# connect_4_robot_trimer_for_sensor.net
KiCad netlist of a schematic drawn in EasyEDA
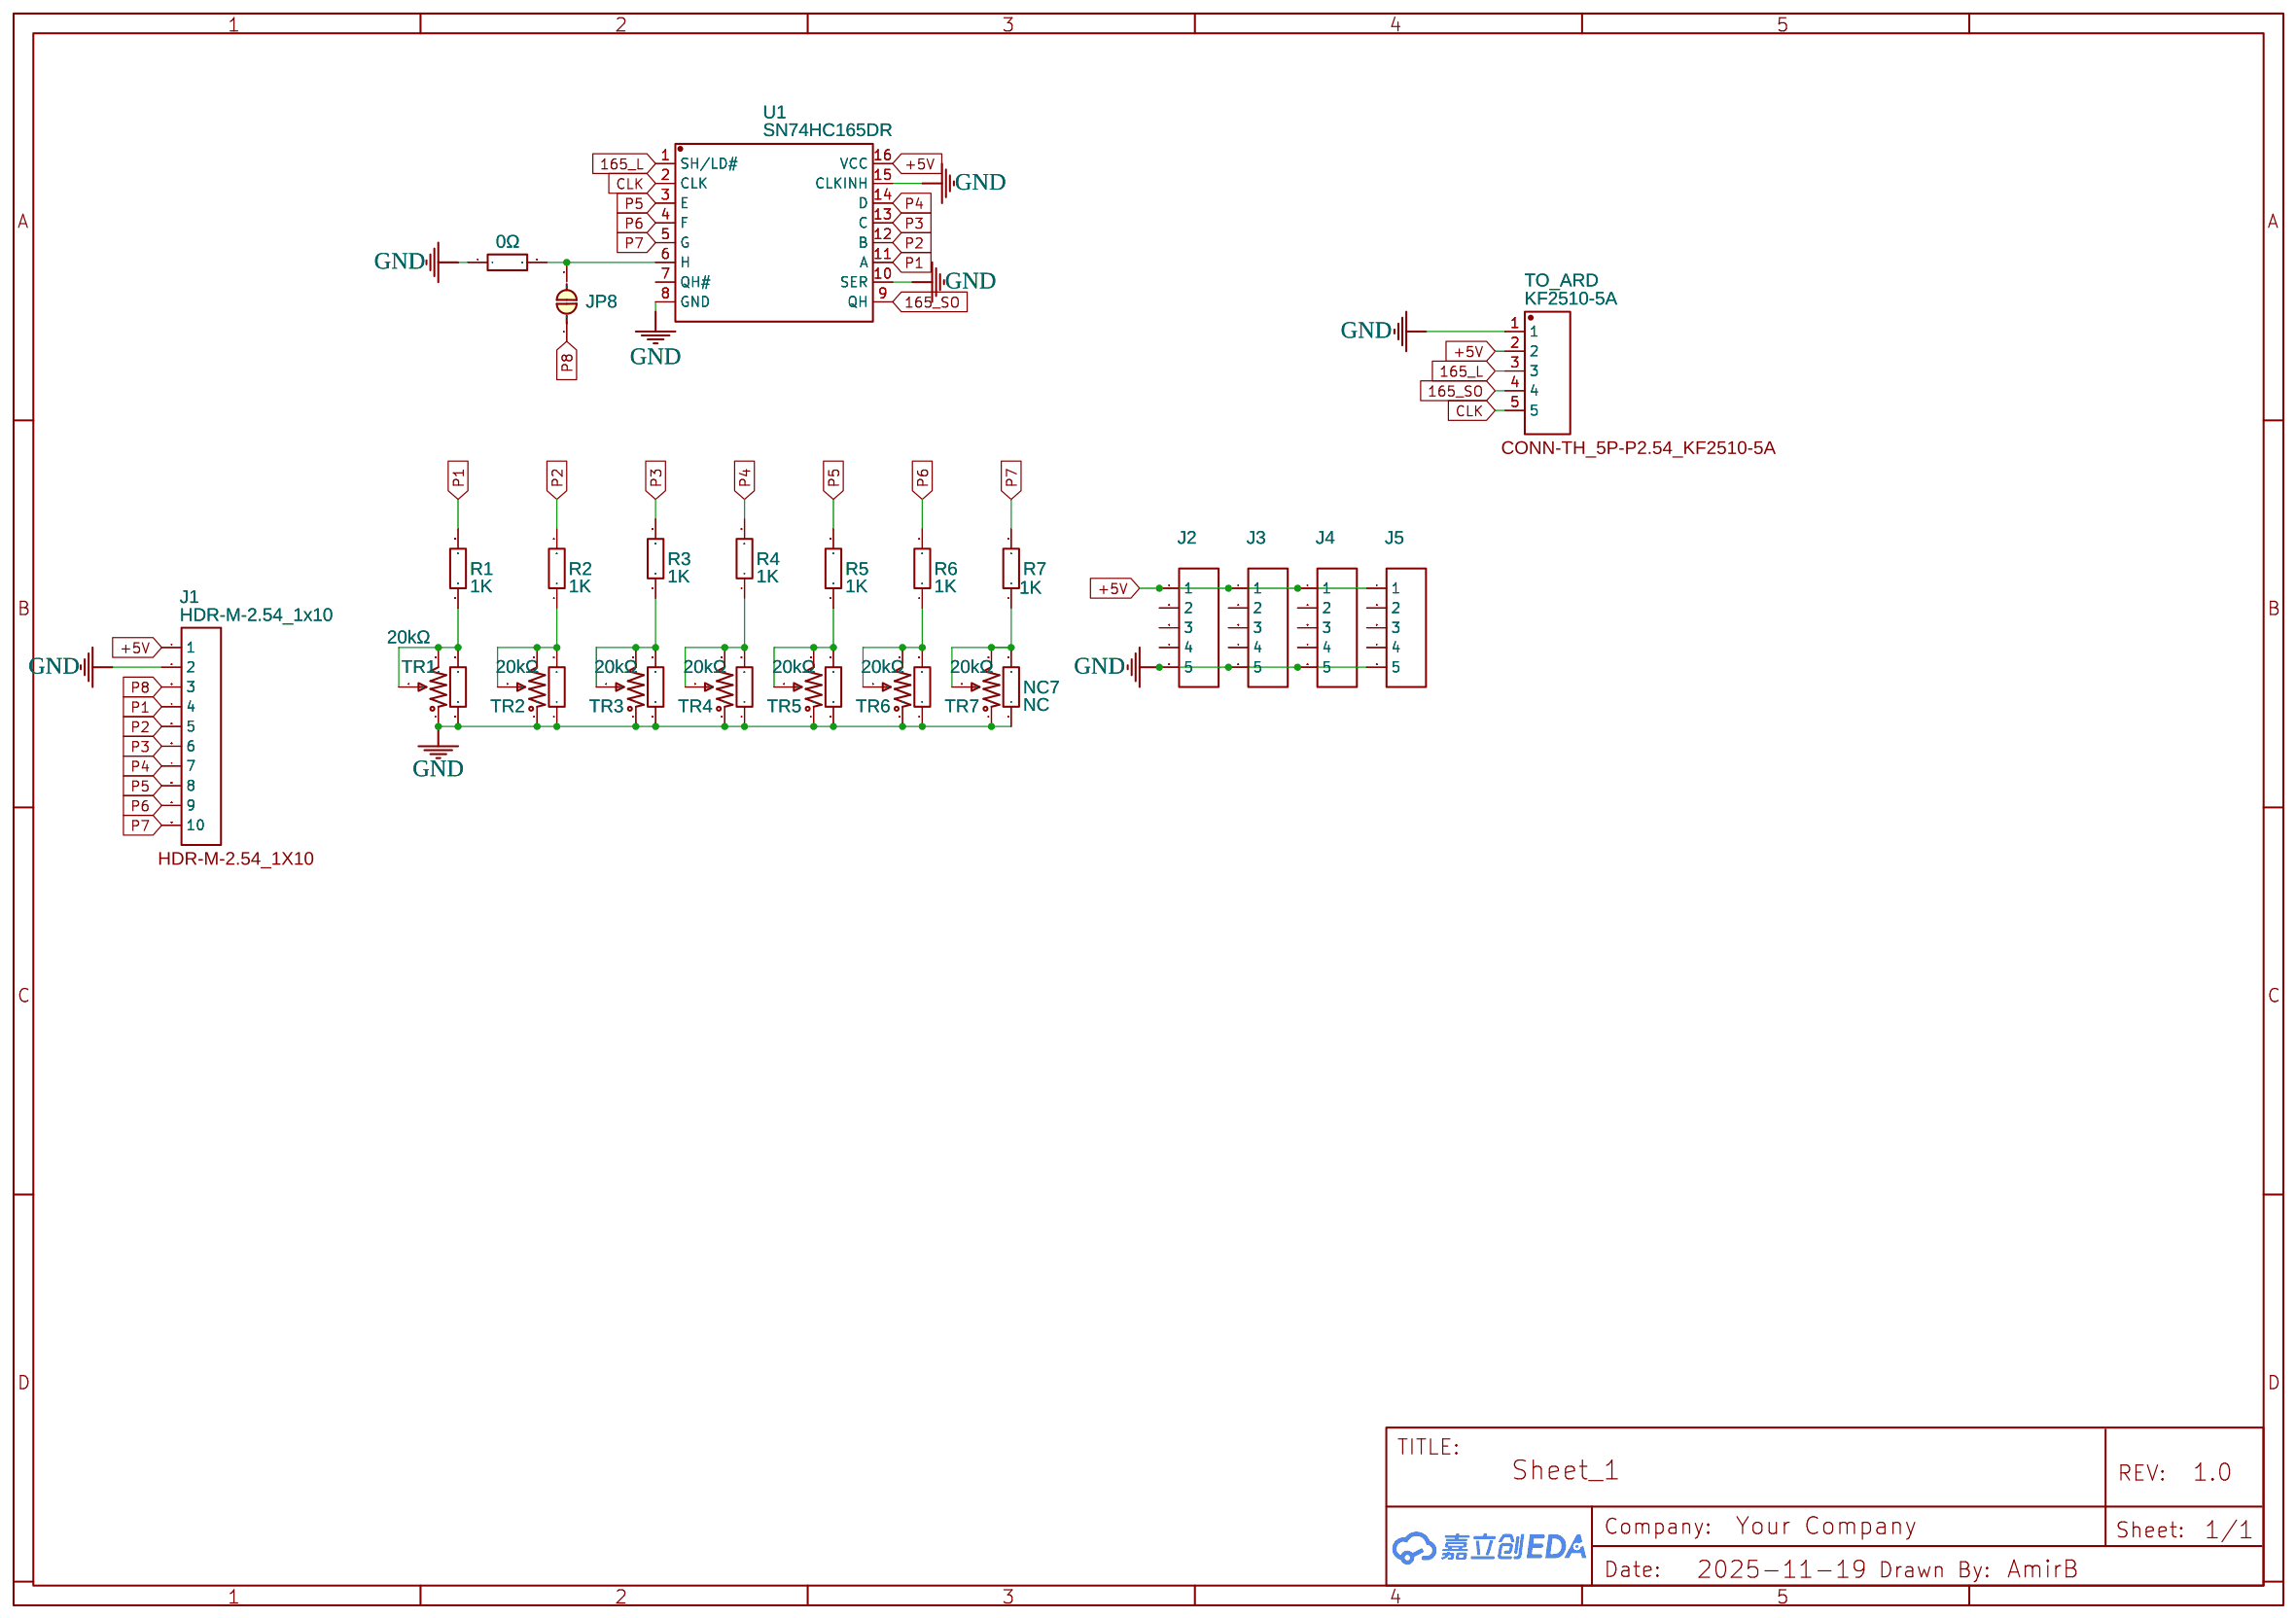
[diagram p0: schematic sheet]

(export (version "E")
  (design (tool "Eeschema 10.0.6"))
  (components
    (comp (ref "J1")
      (value "HDR-M-2.54_1x10")
      (fields (field (name "BOM_Supplier Part") "C57369"))
      (libsource (lib "") (part "HDR-M-2.54_1x10"))
    )
    (comp (ref "J2")
      (value "HDR-M-2.54_1x5")
      (fields (field (name "BOM_Supplier Part") "C358687"))
      (libsource (lib "") (part "HDR-M-2.54_1x5"))
    )
    (comp (ref "J3")
      (value "HDR-M-2.54_1x5")
      (fields (field (name "BOM_Supplier Part") "C358687"))
      (libsource (lib "") (part "HDR-M-2.54_1x5"))
    )
    (comp (ref "J4")
      (value "HDR-M-2.54_1x5")
      (fields (field (name "BOM_Supplier Part") "C358687"))
      (libsource (lib "") (part "HDR-M-2.54_1x5"))
    )
    (comp (ref "J5")
      (value "HDR-M-2.54_1x5")
      (fields (field (name "BOM_Supplier Part") "C358687"))
      (libsource (lib "") (part "HDR-M-2.54_1x5"))
    )
    (comp (ref "JP8") (value "JP") (libsource (lib "") (part "JUMPER-SMT_2")))
    (comp (ref "NC1")
      (value "NC")
      (fields
        (field (name "BOM_Manufacturer Part") "0603WAF1001T5E")
        (field (name "BOM_Supplier Part") "C21190")
      )
      (libsource (lib "") (part "0603WAF1001T5E"))
    )
    (comp (ref "NC2")
      (value "NC")
      (fields
        (field (name "BOM_Manufacturer Part") "0603WAF1001T5E")
        (field (name "BOM_Supplier Part") "C21190")
      )
      (libsource (lib "") (part "0603WAF1001T5E"))
    )
    (comp (ref "NC3")
      (value "NC")
      (fields
        (field (name "BOM_Manufacturer Part") "0603WAF1001T5E")
        (field (name "BOM_Supplier Part") "C21190")
      )
      (libsource (lib "") (part "0603WAF1001T5E"))
    )
    (comp (ref "NC4")
      (value "NC")
      (fields
        (field (name "BOM_Manufacturer Part") "0603WAF1001T5E")
        (field (name "BOM_Supplier Part") "C21190")
      )
      (libsource (lib "") (part "0603WAF1001T5E"))
    )
    (comp (ref "NC5")
      (value "NC")
      (fields
        (field (name "BOM_Manufacturer Part") "0603WAF1001T5E")
        (field (name "BOM_Supplier Part") "C21190")
      )
      (libsource (lib "") (part "0603WAF1001T5E"))
    )
    (comp (ref "NC6")
      (value "NC")
      (fields
        (field (name "BOM_Manufacturer Part") "0603WAF1001T5E")
        (field (name "BOM_Supplier Part") "C21190")
      )
      (libsource (lib "") (part "0603WAF1001T5E"))
    )
    (comp (ref "NC7")
      (value "NC")
      (fields
        (field (name "BOM_Manufacturer Part") "0603WAF1001T5E")
        (field (name "BOM_Supplier Part") "C21190")
      )
      (libsource (lib "") (part "0603WAF1001T5E"))
    )
    (comp (ref "R0")
      (value "0Ω")
      (fields
        (field (name "Manufacturer Part") "0603WAF0000T5E")
        (field (name "Manufacturer") "UNI-ROYAL(厚声)")
      )
      (libsource (lib "") (part "0603WAF0000T5E"))
    )
    (comp (ref "R1")
      (value "1K")
      (fields
        (field (name "BOM_Manufacturer Part") "0603WAF1001T5E")
        (field (name "BOM_Supplier Part") "C21190")
      )
      (libsource (lib "") (part "0603WAF1001T5E_1"))
    )
    (comp (ref "R2")
      (value "1K")
      (fields
        (field (name "BOM_Manufacturer Part") "0603WAF1001T5E")
        (field (name "BOM_Supplier Part") "C21190")
      )
      (libsource (lib "") (part "0603WAF1001T5E_1"))
    )
    (comp (ref "R3")
      (value "1K")
      (fields
        (field (name "BOM_Manufacturer Part") "0603WAF1001T5E")
        (field (name "BOM_Supplier Part") "C21190")
      )
      (libsource (lib "") (part "0603WAF1001T5E_1"))
    )
    (comp (ref "R4")
      (value "1K")
      (fields
        (field (name "BOM_Manufacturer Part") "0603WAF1001T5E")
        (field (name "BOM_Supplier Part") "C21190")
      )
      (libsource (lib "") (part "0603WAF1001T5E_1"))
    )
    (comp (ref "R5")
      (value "1K")
      (fields
        (field (name "BOM_Manufacturer Part") "0603WAF1001T5E")
        (field (name "BOM_Supplier Part") "C21190")
      )
      (libsource (lib "") (part "0603WAF1001T5E_1"))
    )
    (comp (ref "R6")
      (value "1K")
      (fields
        (field (name "BOM_Manufacturer Part") "0603WAF1001T5E")
        (field (name "BOM_Supplier Part") "C21190")
      )
      (libsource (lib "") (part "0603WAF1001T5E_1"))
    )
    (comp (ref "R7")
      (value "1K")
      (fields
        (field (name "BOM_Manufacturer Part") "0603WAF1001T5E")
        (field (name "BOM_Supplier Part") "C21190")
      )
      (libsource (lib "") (part "0603WAF1001T5E_1"))
    )
    (comp (ref "TO_ARD")
      (value "KF2510-5A")
      (fields (field (name "Manufacturer Part") "2510-5A") (field (name "Manufacturer") "BOOMELE(博穆精密)"))
      (libsource (lib "") (part "KF2510-5A"))
    )
    (comp (ref "TR1")
      (value "20kΩ")
      (fields (field (name "Manufacturer Part") "3296W-1-202LF") (field (name "Manufacturer") "JIERR(捷而瑞)"))
      (libsource (lib "") (part "3296W-1-202LF_C49190458"))
    )
    (comp (ref "TR2")
      (value "20kΩ")
      (fields (field (name "Manufacturer Part") "3296W-1-202LF") (field (name "Manufacturer") "JIERR(捷而瑞)"))
      (libsource (lib "") (part "3296W-1-202LF_C49190458"))
    )
    (comp (ref "TR3")
      (value "20kΩ")
      (fields (field (name "Manufacturer Part") "3296W-1-202LF") (field (name "Manufacturer") "JIERR(捷而瑞)"))
      (libsource (lib "") (part "3296W-1-202LF_C49190458"))
    )
    (comp (ref "TR4")
      (value "20kΩ")
      (fields (field (name "Manufacturer Part") "3296W-1-202LF") (field (name "Manufacturer") "JIERR(捷而瑞)"))
      (libsource (lib "") (part "3296W-1-202LF_C49190458"))
    )
    (comp (ref "TR5")
      (value "20kΩ")
      (fields (field (name "Manufacturer Part") "3296W-1-202LF") (field (name "Manufacturer") "JIERR(捷而瑞)"))
      (libsource (lib "") (part "3296W-1-202LF_C49190458"))
    )
    (comp (ref "TR6")
      (value "20kΩ")
      (fields (field (name "Manufacturer Part") "3296W-1-202LF") (field (name "Manufacturer") "JIERR(捷而瑞)"))
      (libsource (lib "") (part "3296W-1-202LF_C49190458"))
    )
    (comp (ref "TR7")
      (value "20kΩ")
      (fields (field (name "Manufacturer Part") "3296W-1-202LF") (field (name "Manufacturer") "JIERR(捷而瑞)"))
      (libsource (lib "") (part "3296W-1-202LF_C49190458"))
    )
    (comp (ref "U1")
      (value "SN74HC165DR")
      (fields (field (name "Manufacturer") "TI(德州仪器)"))
      (libsource (lib "") (part "SN74HC165DR"))
    )
  )
  (nets
    (net (code "1") (name "+5V") (class "Default")
      (node (ref "J1") (pin "1") (pinfunction "1_1") (pintype "unspecified"))
      (node (ref "J2") (pin "1") (pinfunction "1_1") (pintype "unspecified"))
      (node (ref "J3") (pin "1") (pinfunction "1_1") (pintype "unspecified"))
      (node (ref "J4") (pin "1") (pinfunction "1_1") (pintype "unspecified"))
      (node (ref "J5") (pin "1") (pinfunction "1_1") (pintype "unspecified"))
      (node (ref "TO_ARD") (pin "2") (pinfunction "2_2") (pintype "unspecified"))
      (node (ref "U1") (pin "16") (pinfunction "VCC_16") (pintype "unspecified"))
    )
    (net (code "2") (name "165_L") (class "Default")
      (node (ref "TO_ARD") (pin "3") (pinfunction "3_3") (pintype "unspecified"))
      (node (ref "U1") (pin "1") (pinfunction "SH/LD#_1") (pintype "unspecified"))
    )
    (net (code "3") (name "165_SO") (class "Default")
      (node (ref "TO_ARD") (pin "4") (pinfunction "4_4") (pintype "unspecified"))
      (node (ref "U1") (pin "9") (pinfunction "QH_9") (pintype "unspecified"))
    )
    (net (code "4") (name "CLK") (class "Default")
      (node (ref "TO_ARD") (pin "5") (pinfunction "5_5") (pintype "unspecified"))
      (node (ref "U1") (pin "2") (pinfunction "CLK_2") (pintype "unspecified"))
    )
    (net (code "5") (name "GND") (class "Default")
      (node (ref "J1") (pin "2") (pinfunction "2_2") (pintype "unspecified"))
      (node (ref "J2") (pin "5") (pinfunction "5_5") (pintype "unspecified"))
      (node (ref "J3") (pin "5") (pinfunction "5_5") (pintype "unspecified"))
      (node (ref "J4") (pin "5") (pinfunction "5_5") (pintype "unspecified"))
      (node (ref "J5") (pin "5") (pinfunction "5_5") (pintype "unspecified"))
      (node (ref "NC1") (pin "1") (pinfunction "1_1") (pintype "input"))
      (node (ref "NC2") (pin "1") (pinfunction "1_1") (pintype "input"))
      (node (ref "NC3") (pin "1") (pinfunction "1_1") (pintype "input"))
      (node (ref "NC4") (pin "1") (pinfunction "1_1") (pintype "input"))
      (node (ref "NC5") (pin "1") (pinfunction "1_1") (pintype "input"))
      (node (ref "NC6") (pin "1") (pinfunction "1_1") (pintype "input"))
      (node (ref "NC7") (pin "1") (pinfunction "1_1") (pintype "input"))
      (node (ref "R0") (pin "1") (pinfunction "1_1") (pintype "input"))
      (node (ref "TO_ARD") (pin "1") (pinfunction "1_1") (pintype "unspecified"))
      (node (ref "TR1") (pin "1") (pinfunction "1_1") (pintype "unspecified"))
      (node (ref "TR2") (pin "1") (pinfunction "1_1") (pintype "unspecified"))
      (node (ref "TR3") (pin "1") (pinfunction "1_1") (pintype "unspecified"))
      (node (ref "TR4") (pin "1") (pinfunction "1_1") (pintype "unspecified"))
      (node (ref "TR5") (pin "1") (pinfunction "1_1") (pintype "unspecified"))
      (node (ref "TR6") (pin "1") (pinfunction "1_1") (pintype "unspecified"))
      (node (ref "TR7") (pin "1") (pinfunction "1_1") (pintype "unspecified"))
      (node (ref "U1") (pin "10") (pinfunction "SER_10") (pintype "unspecified"))
      (node (ref "U1") (pin "15") (pinfunction "CLKINH_15") (pintype "unspecified"))
      (node (ref "U1") (pin "8") (pinfunction "GND_8") (pintype "unspecified"))
    )
    (net (code "6") (name "Net-(NC1-Pad2)") (class "Default")
      (node (ref "NC1") (pin "2") (pinfunction "2_2") (pintype "input"))
      (node (ref "R1") (pin "1") (pinfunction "1_1") (pintype "input"))
      (node (ref "TR1") (pin "2") (pinfunction "2_2") (pintype "unspecified"))
      (node (ref "TR1") (pin "3") (pinfunction "3_3") (pintype "unspecified"))
    )
    (net (code "7") (name "Net-(NC2-Pad2)") (class "Default")
      (node (ref "NC2") (pin "2") (pinfunction "2_2") (pintype "input"))
      (node (ref "R2") (pin "1") (pinfunction "1_1") (pintype "input"))
      (node (ref "TR2") (pin "2") (pinfunction "2_2") (pintype "unspecified"))
      (node (ref "TR2") (pin "3") (pinfunction "3_3") (pintype "unspecified"))
    )
    (net (code "8") (name "Net-(NC3-Pad2)") (class "Default")
      (node (ref "NC3") (pin "2") (pinfunction "2_2") (pintype "input"))
      (node (ref "R3") (pin "1") (pinfunction "1_1") (pintype "input"))
      (node (ref "TR3") (pin "2") (pinfunction "2_2") (pintype "unspecified"))
      (node (ref "TR3") (pin "3") (pinfunction "3_3") (pintype "unspecified"))
    )
    (net (code "9") (name "Net-(NC4-Pad2)") (class "Default")
      (node (ref "NC4") (pin "2") (pinfunction "2_2") (pintype "input"))
      (node (ref "R4") (pin "1") (pinfunction "1_1") (pintype "input"))
      (node (ref "TR4") (pin "2") (pinfunction "2_2") (pintype "unspecified"))
      (node (ref "TR4") (pin "3") (pinfunction "3_3") (pintype "unspecified"))
    )
    (net (code "10") (name "Net-(NC5-Pad2)") (class "Default")
      (node (ref "NC5") (pin "2") (pinfunction "2_2") (pintype "input"))
      (node (ref "R5") (pin "1") (pinfunction "1_1") (pintype "input"))
      (node (ref "TR5") (pin "2") (pinfunction "2_2") (pintype "unspecified"))
      (node (ref "TR5") (pin "3") (pinfunction "3_3") (pintype "unspecified"))
    )
    (net (code "11") (name "Net-(NC6-Pad2)") (class "Default")
      (node (ref "NC6") (pin "2") (pinfunction "2_2") (pintype "input"))
      (node (ref "R6") (pin "1") (pinfunction "1_1") (pintype "input"))
      (node (ref "TR6") (pin "2") (pinfunction "2_2") (pintype "unspecified"))
      (node (ref "TR6") (pin "3") (pinfunction "3_3") (pintype "unspecified"))
    )
    (net (code "12") (name "Net-(NC7-Pad2)") (class "Default")
      (node (ref "NC7") (pin "2") (pinfunction "2_2") (pintype "input"))
      (node (ref "R7") (pin "1") (pinfunction "1_1") (pintype "input"))
      (node (ref "TR7") (pin "2") (pinfunction "2_2") (pintype "unspecified"))
      (node (ref "TR7") (pin "3") (pinfunction "3_3") (pintype "unspecified"))
    )
    (net (code "13") (name "Net-(U1-H)") (class "Default")
      (node (ref "JP8") (pin "2") (pinfunction "2_2") (pintype "bidirectional"))
      (node (ref "R0") (pin "2") (pinfunction "2_2") (pintype "input"))
      (node (ref "U1") (pin "6") (pinfunction "H_6") (pintype "unspecified"))
    )
    (net (code "14") (name "P1") (class "Default")
      (node (ref "J1") (pin "4") (pinfunction "4_4") (pintype "unspecified"))
      (node (ref "R1") (pin "2") (pinfunction "2_2") (pintype "input"))
      (node (ref "U1") (pin "11") (pinfunction "A_11") (pintype "unspecified"))
    )
    (net (code "15") (name "P2") (class "Default")
      (node (ref "J1") (pin "5") (pinfunction "5_5") (pintype "unspecified"))
      (node (ref "R2") (pin "2") (pinfunction "2_2") (pintype "input"))
      (node (ref "U1") (pin "12") (pinfunction "B_12") (pintype "unspecified"))
    )
    (net (code "16") (name "P3") (class "Default")
      (node (ref "J1") (pin "6") (pinfunction "6_6") (pintype "unspecified"))
      (node (ref "R3") (pin "2") (pinfunction "2_2") (pintype "input"))
      (node (ref "U1") (pin "13") (pinfunction "C_13") (pintype "unspecified"))
    )
    (net (code "17") (name "P4") (class "Default")
      (node (ref "J1") (pin "7") (pinfunction "7_7") (pintype "unspecified"))
      (node (ref "R4") (pin "2") (pinfunction "2_2") (pintype "input"))
      (node (ref "U1") (pin "14") (pinfunction "D_14") (pintype "unspecified"))
    )
    (net (code "18") (name "P5") (class "Default")
      (node (ref "J1") (pin "8") (pinfunction "8_8") (pintype "unspecified"))
      (node (ref "R5") (pin "2") (pinfunction "2_2") (pintype "input"))
      (node (ref "U1") (pin "3") (pinfunction "E_3") (pintype "unspecified"))
    )
    (net (code "19") (name "P6") (class "Default")
      (node (ref "J1") (pin "9") (pinfunction "9_9") (pintype "unspecified"))
      (node (ref "R6") (pin "2") (pinfunction "2_2") (pintype "input"))
      (node (ref "U1") (pin "4") (pinfunction "F_4") (pintype "unspecified"))
    )
    (net (code "20") (name "P7") (class "Default")
      (node (ref "J1") (pin "10") (pinfunction "10_10") (pintype "unspecified"))
      (node (ref "R7") (pin "2") (pinfunction "2_2") (pintype "input"))
      (node (ref "U1") (pin "5") (pinfunction "G_5") (pintype "unspecified"))
    )
    (net (code "21") (name "P8") (class "Default")
      (node (ref "J1") (pin "3") (pinfunction "3_3") (pintype "unspecified"))
      (node (ref "JP8") (pin "1") (pinfunction "1_1") (pintype "bidirectional"))
    )
    (net (code "22") (name "unconnected-(J2-Pad2)") (class "Default")
      (node (ref "J2") (pin "2") (pinfunction "2_2") (pintype "unspecified"))
    )
    (net (code "23") (name "unconnected-(J2-Pad3)") (class "Default")
      (node (ref "J2") (pin "3") (pinfunction "3_3") (pintype "unspecified"))
    )
    (net (code "24") (name "unconnected-(J2-Pad4)") (class "Default")
      (node (ref "J2") (pin "4") (pinfunction "4_4") (pintype "unspecified"))
    )
    (net (code "25") (name "unconnected-(J3-Pad2)") (class "Default")
      (node (ref "J3") (pin "2") (pinfunction "2_2") (pintype "unspecified"))
    )
    (net (code "26") (name "unconnected-(J3-Pad3)") (class "Default")
      (node (ref "J3") (pin "3") (pinfunction "3_3") (pintype "unspecified"))
    )
    (net (code "27") (name "unconnected-(J3-Pad4)") (class "Default")
      (node (ref "J3") (pin "4") (pinfunction "4_4") (pintype "unspecified"))
    )
    (net (code "28") (name "unconnected-(J4-Pad2)") (class "Default")
      (node (ref "J4") (pin "2") (pinfunction "2_2") (pintype "unspecified"))
    )
    (net (code "29") (name "unconnected-(J4-Pad3)") (class "Default")
      (node (ref "J4") (pin "3") (pinfunction "3_3") (pintype "unspecified"))
    )
    (net (code "30") (name "unconnected-(J4-Pad4)") (class "Default")
      (node (ref "J4") (pin "4") (pinfunction "4_4") (pintype "unspecified"))
    )
    (net (code "31") (name "unconnected-(J5-Pad2)") (class "Default")
      (node (ref "J5") (pin "2") (pinfunction "2_2") (pintype "unspecified"))
    )
    (net (code "32") (name "unconnected-(J5-Pad3)") (class "Default")
      (node (ref "J5") (pin "3") (pinfunction "3_3") (pintype "unspecified"))
    )
    (net (code "33") (name "unconnected-(J5-Pad4)") (class "Default")
      (node (ref "J5") (pin "4") (pinfunction "4_4") (pintype "unspecified"))
    )
    (net (code "34") (name "unconnected-(U1-QH#-Pad7)") (class "Default")
      (node (ref "U1") (pin "7") (pinfunction "QH#_7") (pintype "unspecified"))
    )
  )
)
